# Sheet_1.net
KiCad netlist of a schematic drawn in Altium Designer
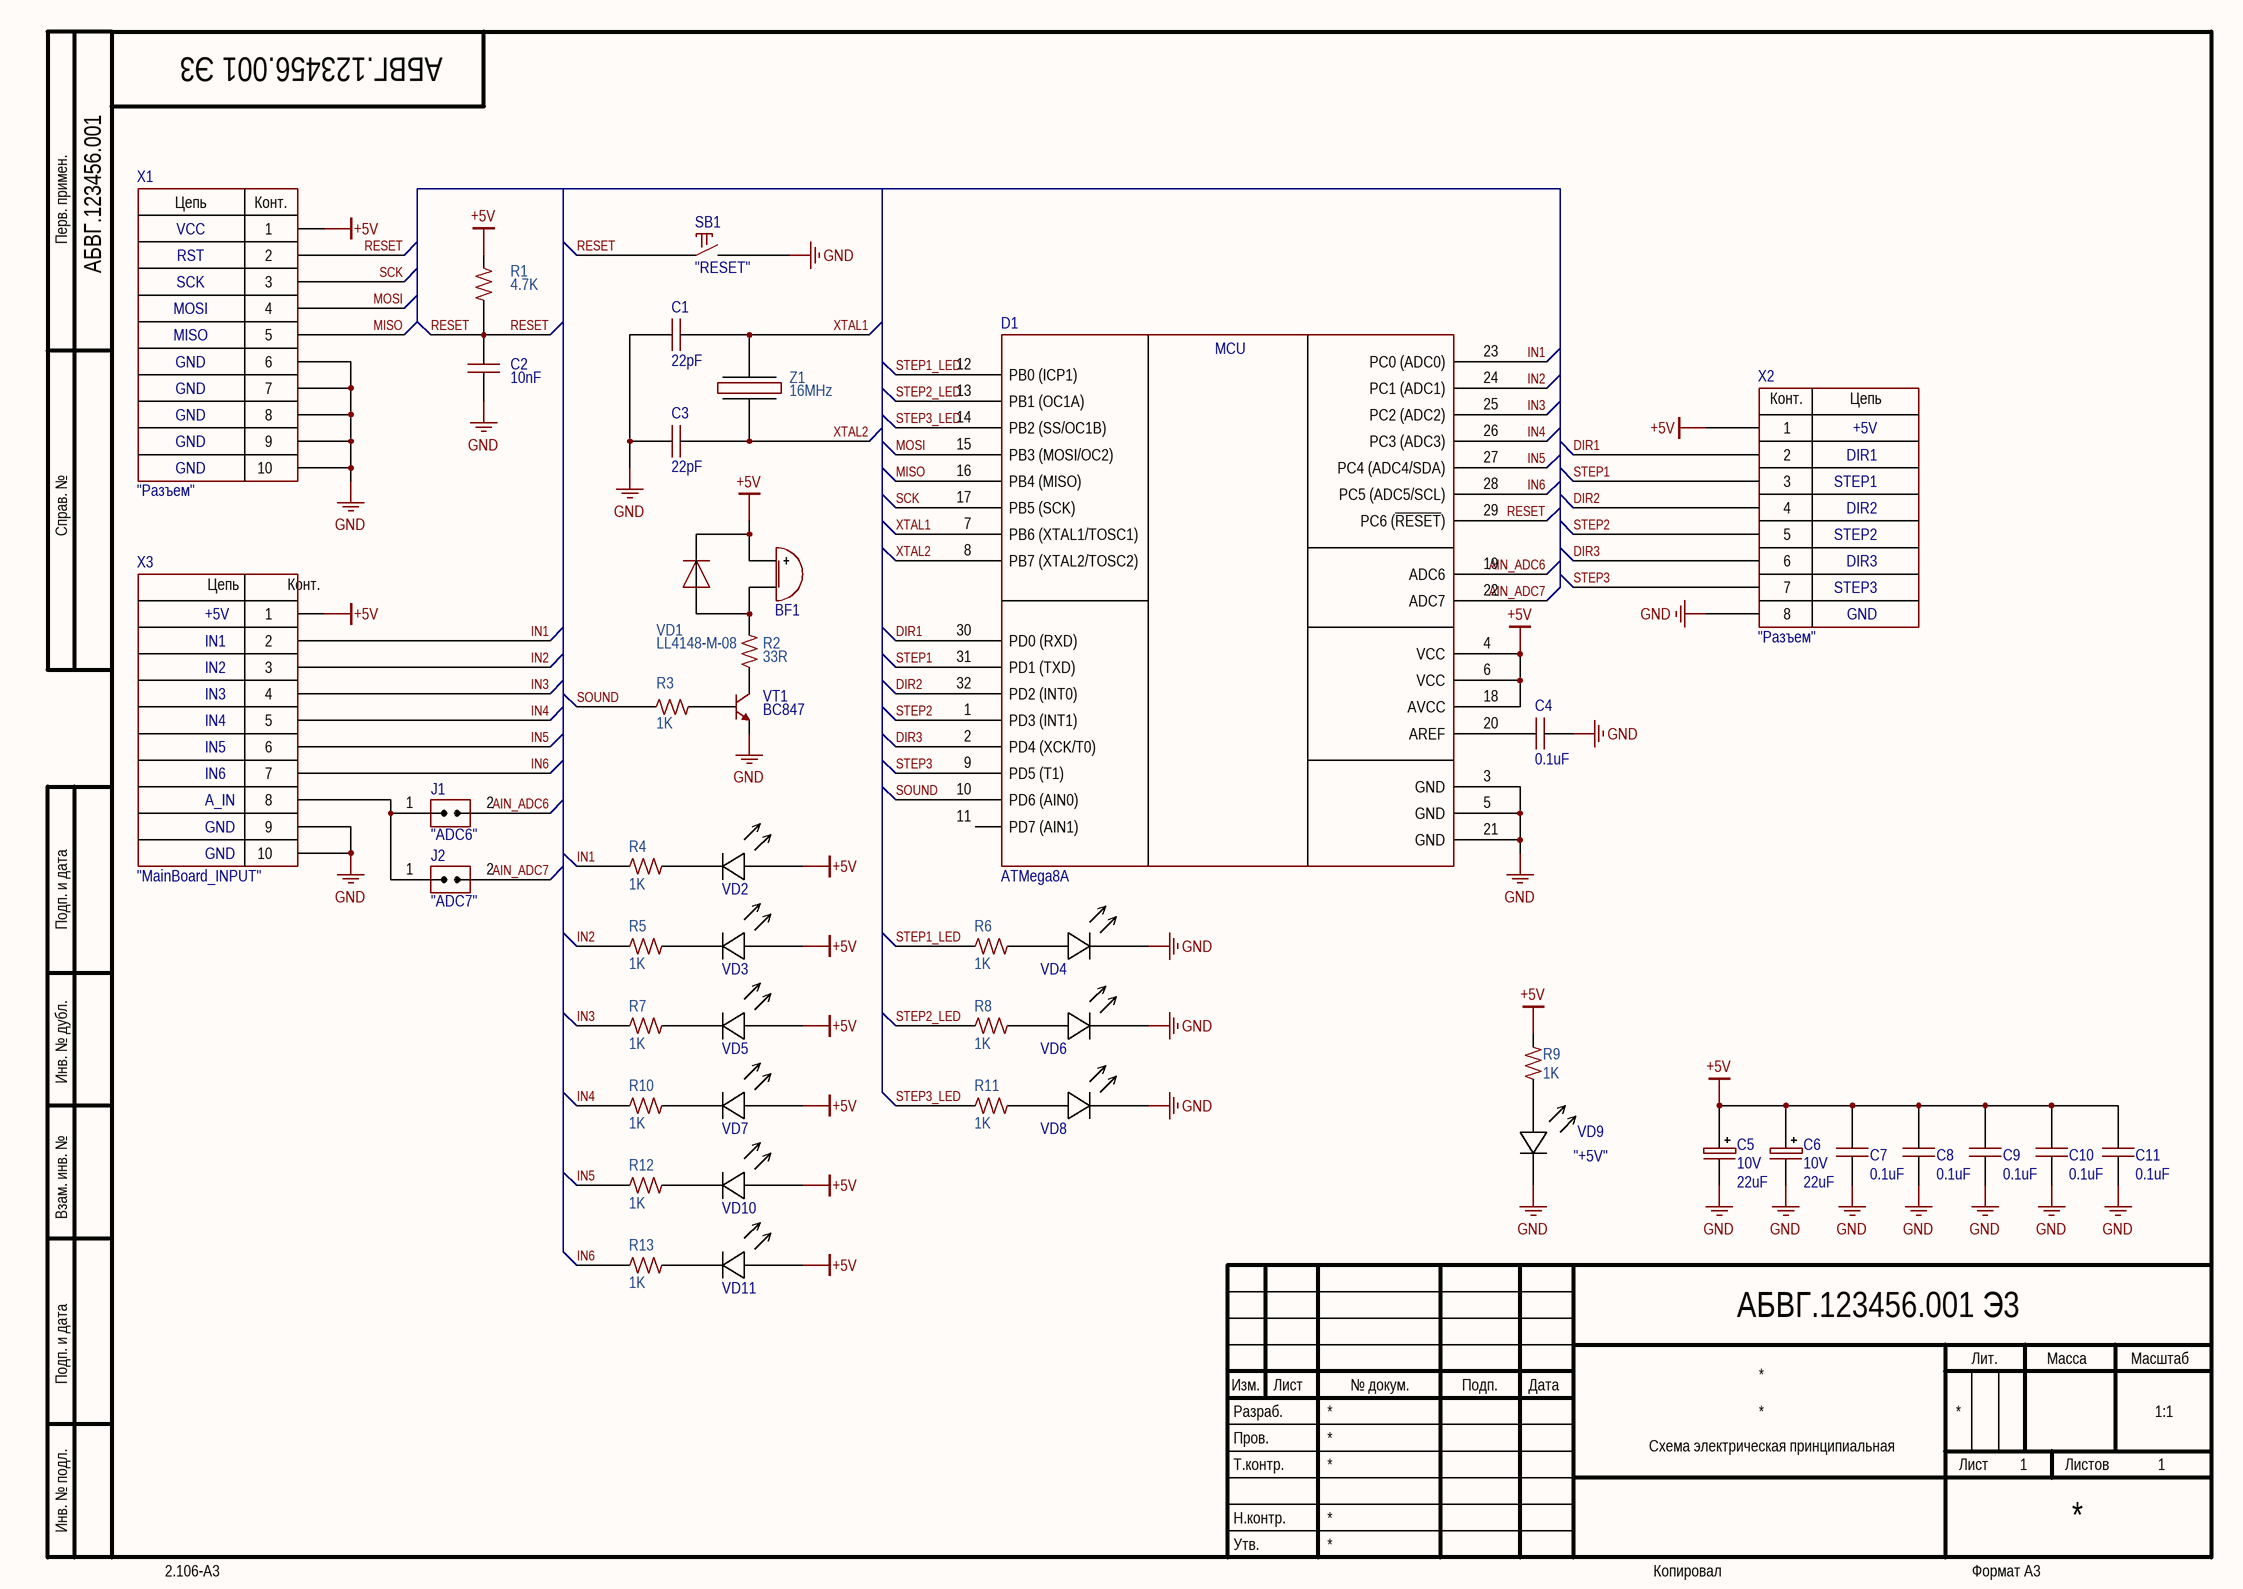
[diagram p0: Sheet_1.SchDoc]

(export (version "E")
  (design (tool "Eeschema 10.0.6"))
  (components
    (comp (ref "BF1")
      (value "~")
      (footprint "Custom_Case:BUZ: AI-1223-TWT-3V-2-R")
      (fields
        (field (name "MANUFACTURER") "PUI Audio")
        (field (name "VALUEMANUFACTURERPARTNUMBER") "DIP switch, 2.73 kHz, 3VDC, 80mA, -20...+70°C")
        (field (name "PARTNUMBER") "AT-0927-TT-6-R")
      )
      (libsource (lib "Electromechanics") (part "Buzzer"))
    )
    (comp (ref "C1")
      (value "Керамический SMD")
      (footprint "Standart_Case:CAP: 0805")
      (fields (field (name "ЗНАЧЕНИЕ") "22pF"))
      (libsource (lib "Capacitor") (part "Керамический SMD"))
    )
    (comp (ref "C2")
      (value "Керамический SMD")
      (footprint "Standart_Case:CAP: 0805")
      (fields (field (name "ЗНАЧЕНИЕ") "10nF"))
      (libsource (lib "Capacitor") (part "Керамический SMD"))
    )
    (comp (ref "C3")
      (value "Керамический SMD")
      (footprint "Standart_Case:CAP: 0805")
      (fields (field (name "ЗНАЧЕНИЕ") "22pF"))
      (libsource (lib "Capacitor") (part "Керамический SMD"))
    )
    (comp (ref "C4")
      (value "Керамический SMD")
      (footprint "Standart_Case:CAP: 0805")
      (fields (field (name "ЗНАЧЕНИЕ") "0.1uF"))
      (libsource (lib "Capacitor") (part "Керамический SMD"))
    )
    (comp (ref "C5")
      (value "~")
      (footprint "Standart_Case:CAP: TANTAL-B")
      (fields (field (name "НАПРЯЖЕНИЕ") "10V") (field (name "ЗНАЧЕНИЕ") "22uF"))
      (libsource (lib "Capacitor") (part "Танталы SMD"))
    )
    (comp (ref "C6")
      (value "~")
      (footprint "Standart_Case:CAP: TANTAL-B")
      (fields (field (name "НАПРЯЖЕНИЕ") "10V") (field (name "ЗНАЧЕНИЕ") "22uF"))
      (libsource (lib "Capacitor") (part "Танталы SMD"))
    )
    (comp (ref "C7")
      (value "Керамический SMD")
      (footprint "Standart_Case:CAP: 0805")
      (fields (field (name "ЗНАЧЕНИЕ") "0.1uF"))
      (libsource (lib "Capacitor") (part "Керамический SMD"))
    )
    (comp (ref "C8")
      (value "Керамический SMD")
      (footprint "Standart_Case:CAP: 0805")
      (fields (field (name "ЗНАЧЕНИЕ") "0.1uF"))
      (libsource (lib "Capacitor") (part "Керамический SMD"))
    )
    (comp (ref "C9")
      (value "Керамический SMD")
      (footprint "Standart_Case:CAP: 0805")
      (fields (field (name "ЗНАЧЕНИЕ") "0.1uF"))
      (libsource (lib "Capacitor") (part "Керамический SMD"))
    )
    (comp (ref "C10")
      (value "Керамический SMD")
      (footprint "Standart_Case:CAP: 0805")
      (fields (field (name "ЗНАЧЕНИЕ") "0.1uF"))
      (libsource (lib "Capacitor") (part "Керамический SMD"))
    )
    (comp (ref "C11")
      (value "Керамический SMD")
      (footprint "Standart_Case:CAP: 0805")
      (fields (field (name "ЗНАЧЕНИЕ") "0.1uF"))
      (libsource (lib "Capacitor") (part "Керамический SMD"))
    )
    (comp (ref "D1")
      (value "ATMega8A")
      (footprint "Standart_Case:32-LQFP")
      (libsource (lib "IC_MCU") (part "ATmega8"))
    )
    (comp (ref "J1")
      (value "~")
      (footprint "Custom_Case:CON: JUMPER x1")
      (fields (field (name "COMMENTTEXT") "\"ADC6\""))
      (libsource (lib "Connector") (part "Jumper_2_pin"))
    )
    (comp (ref "J2")
      (value "~")
      (footprint "Custom_Case:CON: JUMPER x1")
      (fields (field (name "COMMENTTEXT") "\"ADC7\""))
      (libsource (lib "Connector") (part "Jumper_2_pin"))
    )
    (comp (ref "R1")
      (value "4.7K")
      (footprint "Standart_Case:RES: 0805")
      (fields
        (field (name "MANUFACTURER") "Vishay Intertech")
        (field (name "PARTNUMBER") "CRCW080533R0FKEA")
        (field (name "VALUEMANUFACTURERPARTNUMBER") "Резистор SMD, 4.7K, ±1%, 0805, 0.125W, -55...+125°C")
      )
      (libsource (lib "Resistor") (part "Resistor_0805_ieee"))
    )
    (comp (ref "R2")
      (value "33R")
      (footprint "Standart_Case:RES: 0805")
      (fields
        (field (name "MANUFACTURER") "Vishay Intertech")
        (field (name "PARTNUMBER") "CRCW080533R0FKEA")
        (field (name "VALUEMANUFACTURERPARTNUMBER") "Резистор SMD, 33R, ±1%, 0805, 0.125W, -55...+125°C")
      )
      (libsource (lib "Resistor") (part "Resistor_0805_ieee"))
    )
    (comp (ref "R3")
      (value "1K")
      (footprint "Standart_Case:RES: 0805")
      (fields
        (field (name "MANUFACTURER") "Vishay Intertech")
        (field (name "PARTNUMBER") "CRCW08051K00JNEA")
        (field (name "VALUEMANUFACTURERPARTNUMBER") "Резистор SMD, 1K, ±1%, 0805, 0.125W, -55...+125°C")
      )
      (libsource (lib "Resistor") (part "Resistor_0805_ieee"))
    )
    (comp (ref "R4")
      (value "1K")
      (footprint "Standart_Case:RES: 0805")
      (fields
        (field (name "MANUFACTURER") "Vishay Intertech")
        (field (name "PARTNUMBER") "CRCW080533R0FKEA")
        (field (name "VALUEMANUFACTURERPARTNUMBER") "Резистор SMD, 1K, ±1%, 0805, 0.125W, -55...+125°C")
      )
      (libsource (lib "Resistor") (part "Resistor_0805_ieee"))
    )
    (comp (ref "R5")
      (value "1K")
      (footprint "Standart_Case:RES: 0805")
      (fields
        (field (name "MANUFACTURER") "Vishay Intertech")
        (field (name "PARTNUMBER") "CRCW080533R0FKEA")
        (field (name "VALUEMANUFACTURERPARTNUMBER") "Резистор SMD, 1K, ±1%, 0805, 0.125W, -55...+125°C")
      )
      (libsource (lib "Resistor") (part "Resistor_0805_ieee"))
    )
    (comp (ref "R6")
      (value "1K")
      (footprint "Standart_Case:RES: 0805")
      (fields
        (field (name "MANUFACTURER") "Vishay Intertech")
        (field (name "PARTNUMBER") "CRCW080533R0FKEA")
        (field (name "VALUEMANUFACTURERPARTNUMBER") "Резистор SMD, 1K, ±1%, 0805, 0.125W, -55...+125°C")
      )
      (libsource (lib "Resistor") (part "Resistor_0805_ieee"))
    )
    (comp (ref "R7")
      (value "1K")
      (footprint "Standart_Case:RES: 0805")
      (fields
        (field (name "MANUFACTURER") "Vishay Intertech")
        (field (name "PARTNUMBER") "CRCW080533R0FKEA")
        (field (name "VALUEMANUFACTURERPARTNUMBER") "Резистор SMD, 1K, ±1%, 0805, 0.125W, -55...+125°C")
      )
      (libsource (lib "Resistor") (part "Resistor_0805_ieee"))
    )
    (comp (ref "R8")
      (value "1K")
      (footprint "Standart_Case:RES: 0805")
      (fields
        (field (name "MANUFACTURER") "Vishay Intertech")
        (field (name "PARTNUMBER") "CRCW080533R0FKEA")
        (field (name "VALUEMANUFACTURERPARTNUMBER") "Резистор SMD, 1K, ±1%, 0805, 0.125W, -55...+125°C")
      )
      (libsource (lib "Resistor") (part "Resistor_0805_ieee"))
    )
    (comp (ref "R9")
      (value "1K")
      (footprint "Standart_Case:RES: 0805")
      (fields
        (field (name "MANUFACTURER") "Vishay Intertech")
        (field (name "PARTNUMBER") "CRCW080533R0FKEA")
        (field (name "VALUEMANUFACTURERPARTNUMBER") "Резистор SMD, 1K, ±1%, 0805, 0.125W, -55...+125°C")
      )
      (libsource (lib "Resistor") (part "Resistor_0805_ieee"))
    )
    (comp (ref "R10")
      (value "1K")
      (footprint "Standart_Case:RES: 0805")
      (fields
        (field (name "MANUFACTURER") "Vishay Intertech")
        (field (name "PARTNUMBER") "CRCW080533R0FKEA")
        (field (name "VALUEMANUFACTURERPARTNUMBER") "Резистор SMD, 1K, ±1%, 0805, 0.125W, -55...+125°C")
      )
      (libsource (lib "Resistor") (part "Resistor_0805_ieee"))
    )
    (comp (ref "R11")
      (value "1K")
      (footprint "Standart_Case:RES: 0805")
      (fields
        (field (name "MANUFACTURER") "Vishay Intertech")
        (field (name "PARTNUMBER") "CRCW080533R0FKEA")
        (field (name "VALUEMANUFACTURERPARTNUMBER") "Резистор SMD, 1K, ±1%, 0805, 0.125W, -55...+125°C")
      )
      (libsource (lib "Resistor") (part "Resistor_0805_ieee"))
    )
    (comp (ref "R12")
      (value "1K")
      (footprint "Standart_Case:RES: 0805")
      (fields
        (field (name "MANUFACTURER") "Vishay Intertech")
        (field (name "PARTNUMBER") "CRCW080533R0FKEA")
        (field (name "VALUEMANUFACTURERPARTNUMBER") "Резистор SMD, 1K, ±1%, 0805, 0.125W, -55...+125°C")
      )
      (libsource (lib "Resistor") (part "Resistor_0805_ieee"))
    )
    (comp (ref "R13")
      (value "1K")
      (footprint "Standart_Case:RES: 0805")
      (fields
        (field (name "MANUFACTURER") "Vishay Intertech")
        (field (name "PARTNUMBER") "CRCW080533R0FKEA")
        (field (name "VALUEMANUFACTURERPARTNUMBER") "Резистор SMD, 1K, ±1%, 0805, 0.125W, -55...+125°C")
      )
      (libsource (lib "Resistor") (part "Resistor_0805_ieee"))
    )
    (comp (ref "SB1")
      (value "~")
      (footprint "Custom_Case:BUT: 6x6 SMD")
      (fields
        (field (name "MANUFACTURER") "TE Connectivity")
        (field (name "VALUEMANUFACTURERPARTNUMBER") "Tactile button, 6x6mm")
        (field (name "PARTNUMBER") "FSM2JSMAATR")
        (field (name "COMMENTTEXT") "\"RESET\"")
      )
      (libsource (lib "Electromechanics") (part "Button_tactile"))
    )
    (comp (ref "VD1")
      (value "~")
      (footprint "Standart_Case:DIODE: SOD80")
      (fields
        (field (name "MANUFACTURER") "Vishay Intertech")
        (field (name "VALUEMANUFACTURERPARTNUMBER") "Single diode, 75V, 150mA, 1V, 4ns, SOD-80, -55...+150°C")
        (field (name "VOLTAGE") "75V")
        (field (name "PARTNUMBER") "LL4148-M-08")
      )
      (libsource (lib "Diode") (part "Diode_single"))
    )
    (comp (ref "VD2")
      (value "~")
      (footprint "Standart_Case:LED: 3mmG")
      (fields (field (name "VALUEMANUFACTURERPARTNUMBER") "LED, Green, *, *, *, -55...+150°C"))
      (libsource (lib "Diode") (part "LED_single"))
    )
    (comp (ref "VD3")
      (value "~")
      (footprint "Standart_Case:LED: 3mmG")
      (fields (field (name "VALUEMANUFACTURERPARTNUMBER") "LED, Green, *, *, *, -55...+150°C"))
      (libsource (lib "Diode") (part "LED_single"))
    )
    (comp (ref "VD4")
      (value "~")
      (footprint "Standart_Case:LED: 3mmG")
      (fields (field (name "VALUEMANUFACTURERPARTNUMBER") "LED, Green, *, *, *, -55...+150°C"))
      (libsource (lib "") (part "LED_single_1"))
    )
    (comp (ref "VD5")
      (value "~")
      (footprint "Standart_Case:LED: 3mmG")
      (fields (field (name "VALUEMANUFACTURERPARTNUMBER") "LED, Green, *, *, *, -55...+150°C"))
      (libsource (lib "Diode") (part "LED_single"))
    )
    (comp (ref "VD6")
      (value "~")
      (footprint "Standart_Case:LED: 3mmG")
      (fields (field (name "VALUEMANUFACTURERPARTNUMBER") "LED, Green, *, *, *, -55...+150°C"))
      (libsource (lib "") (part "LED_single_1"))
    )
    (comp (ref "VD7")
      (value "~")
      (footprint "Standart_Case:LED: 3mmG")
      (fields (field (name "VALUEMANUFACTURERPARTNUMBER") "LED, Green, *, *, *, -55...+150°C"))
      (libsource (lib "Diode") (part "LED_single"))
    )
    (comp (ref "VD8")
      (value "~")
      (footprint "Standart_Case:LED: 3mmG")
      (fields (field (name "VALUEMANUFACTURERPARTNUMBER") "LED, Green, *, *, *, -55...+150°C"))
      (libsource (lib "") (part "LED_single_1"))
    )
    (comp (ref "VD9")
      (value "\"+5V\"")
      (footprint "Standart_Case:LED: 3mmB")
      (fields (field (name "VALUEMANUFACTURERPARTNUMBER") "LED, Green, *, *, *, -55...+150°C"))
      (libsource (lib "Diode") (part "LED_single"))
    )
    (comp (ref "VD10")
      (value "~")
      (footprint "Standart_Case:LED: 3mmG")
      (fields (field (name "VALUEMANUFACTURERPARTNUMBER") "LED, Green, *, *, *, -55...+150°C"))
      (libsource (lib "Diode") (part "LED_single"))
    )
    (comp (ref "VD11")
      (value "~")
      (footprint "Standart_Case:LED: 3mmG")
      (fields (field (name "VALUEMANUFACTURERPARTNUMBER") "LED, Green, *, *, *, -55...+150°C"))
      (libsource (lib "Diode") (part "LED_single"))
    )
    (comp (ref "VT1")
      (value "~")
      (footprint "Standart_Case:SOT23")
      (fields
        (field (name "MANUFACTURER") "ON Semiconductor")
        (field (name "VALUEMANUFACTURERPARTNUMBER") "NPN transistor, 45V, 100mA, 100MHz, 300mW, 0.6V, 420, SOT-23, -55...+125°C")
        (field (name "PARTNUMBER") "BC847")
      )
      (libsource (lib "Transistor") (part "BJT_NPN_123"))
    )
    (comp (ref "X1")
      (value "~")
      (footprint "Custom_Case:CON: PROG(PCB) ISP")
      (fields
        (field (name "MANUFACTURER") "Connfly")
        (field (name "VALUEMANUFACTURERPARTNUMBER") "Connector, 6pin, 2.54mm, 250VAC, 3A")
        (field (name "PARTNUMBER") "IDC-6")
        (field (name "COMMENTTEXT") "\"Разъем\"")
      )
      (libsource (lib "Connector") (part "Connector_ISP_PCB"))
    )
    (comp (ref "X2")
      (value "~")
      (footprint "Custom_Case:CON: PLS-8")
      (fields
        (field (name "MANUFACTURER") "Connfly")
        (field (name "VALUEMANUFACTURERPARTNUMBER") "Connector, 8pin, 2.54mm, 500VAC, 3A")
        (field (name "PARTNUMBER") "PLS-8")
        (field (name "COMMENTTEXT") "\"Разъем\"")
      )
      (libsource (lib "Connector") (part "PLS-8"))
    )
    (comp (ref "X3")
      (value "~")
      (footprint "Custom_Case:CON: PLS-10")
      (fields
        (field (name "MANUFACTURER") "Connfly")
        (field (name "VALUEMANUFACTURERPARTNUMBER") "Connector, 10pin, 2.54mm, 500VAC, 3A")
        (field (name "PARTNUMBER") "PLS-10")
        (field (name "COMMENTTEXT") "\"MainBoard_INPUT\"")
      )
      (libsource (lib "Connector") (part "PLS-10"))
    )
    (comp (ref "Z1")
      (value "~")
      (footprint "Custom_Case:OSC: 5032_ABM3")
      (fields
        (field (name "MANUFACTURER") "ABRACON LLC")
        (field (name "PARTNUMBER") "ABM3-16.000MHZ-D2Y-T")
        (field (name "VALUEMANUFACTURERPARTNUMBER") "Crystal, 16MHz, 18pF, ±20ppm, ABM3, -40...+85°C")
        (field (name "FREQUENCY") "16MHz")
      )
      (libsource (lib "Oscilator") (part "Crystal_5032_ABM3"))
    )
  )
  (nets
    (net (code "1") (name "+5V") (class "Default")
      (node (ref "BF1") (pin "1") (pinfunction "+_1") (pintype "passive"))
      (node (ref "C10") (pin "2") (pinfunction "2_2") (pintype "passive"))
      (node (ref "C11") (pin "2") (pinfunction "2_2") (pintype "passive"))
      (node (ref "C5") (pin "1") (pinfunction "1_1") (pintype "passive"))
      (node (ref "C6") (pin "1") (pinfunction "1_1") (pintype "passive"))
      (node (ref "C7") (pin "2") (pinfunction "2_2") (pintype "passive"))
      (node (ref "C8") (pin "2") (pinfunction "2_2") (pintype "passive"))
      (node (ref "C9") (pin "2") (pinfunction "2_2") (pintype "passive"))
      (node (ref "D1") (pin "18") (pinfunction "AVCC_18") (pintype "passive"))
      (node (ref "D1") (pin "4") (pinfunction "VCC_4") (pintype "passive"))
      (node (ref "D1") (pin "6") (pinfunction "VCC_6") (pintype "passive"))
      (node (ref "R1") (pin "1") (pinfunction "1_1") (pintype "passive"))
      (node (ref "R9") (pin "2") (pinfunction "2_2") (pintype "passive"))
      (node (ref "VD1") (pin "2") (pinfunction "2_2") (pintype "passive"))
      (node (ref "VD10") (pin "1") (pinfunction "A_1") (pintype "passive"))
      (node (ref "VD11") (pin "1") (pinfunction "A_1") (pintype "passive"))
      (node (ref "VD2") (pin "1") (pinfunction "A_1") (pintype "passive"))
      (node (ref "VD3") (pin "1") (pinfunction "A_1") (pintype "passive"))
      (node (ref "VD5") (pin "1") (pinfunction "A_1") (pintype "passive"))
      (node (ref "VD7") (pin "1") (pinfunction "A_1") (pintype "passive"))
      (node (ref "X1") (pin "1") (pinfunction "1_1") (pintype "passive"))
      (node (ref "X2") (pin "1") (pinfunction "1_1") (pintype "passive"))
      (node (ref "X3") (pin "1") (pinfunction "1_1") (pintype "passive"))
    )
    (net (code "2") (name "/AIN_ADC6") (class "Default")
      (node (ref "D1") (pin "19") (pinfunction "ADC6_19") (pintype "passive"))
      (node (ref "J1") (pin "2") (pinfunction "IN_2") (pintype "passive"))
    )
    (net (code "3") (name "/AIN_ADC7") (class "Default")
      (node (ref "D1") (pin "22") (pinfunction "ADC7_22") (pintype "passive"))
      (node (ref "J2") (pin "2") (pinfunction "IN_2") (pintype "passive"))
    )
    (net (code "4") (name "/DIR1") (class "Default")
      (node (ref "D1") (pin "30") (pinfunction "PD0_(RXD)_30") (pintype "passive"))
      (node (ref "X2") (pin "2") (pinfunction "2_2") (pintype "passive"))
    )
    (net (code "5") (name "/DIR2") (class "Default")
      (node (ref "D1") (pin "32") (pinfunction "PD2_(INT0)_32") (pintype "passive"))
      (node (ref "X2") (pin "4") (pinfunction "4_4") (pintype "power_in"))
    )
    (net (code "6") (name "/DIR3") (class "Default")
      (node (ref "D1") (pin "2") (pinfunction "PD4_(XCK/T0)_2") (pintype "passive"))
      (node (ref "X2") (pin "6") (pinfunction "6_6") (pintype "power_in"))
    )
    (net (code "7") (name "/IN1") (class "Default")
      (node (ref "D1") (pin "23") (pinfunction "PC0_(ADC0)_23") (pintype "passive"))
      (node (ref "R4") (pin "1") (pinfunction "1_1") (pintype "passive"))
      (node (ref "X3") (pin "2") (pinfunction "2_2") (pintype "passive"))
    )
    (net (code "8") (name "/IN2") (class "Default")
      (node (ref "D1") (pin "24") (pinfunction "PC1_(ADC1)_24") (pintype "passive"))
      (node (ref "R5") (pin "1") (pinfunction "1_1") (pintype "passive"))
      (node (ref "X3") (pin "3") (pinfunction "3_3") (pintype "power_in"))
    )
    (net (code "9") (name "/IN3") (class "Default")
      (node (ref "D1") (pin "25") (pinfunction "PC2_(ADC2)_25") (pintype "passive"))
      (node (ref "R7") (pin "1") (pinfunction "1_1") (pintype "passive"))
      (node (ref "X3") (pin "4") (pinfunction "4_4") (pintype "power_in"))
    )
    (net (code "10") (name "/IN4") (class "Default")
      (node (ref "D1") (pin "26") (pinfunction "PC3_(ADC3)_26") (pintype "passive"))
      (node (ref "R10") (pin "1") (pinfunction "1_1") (pintype "passive"))
      (node (ref "X3") (pin "5") (pinfunction "5_5") (pintype "power_in"))
    )
    (net (code "11") (name "/IN5") (class "Default")
      (node (ref "D1") (pin "27") (pinfunction "PC4_(ADC4/SDA)_27") (pintype "passive"))
      (node (ref "R12") (pin "1") (pinfunction "1_1") (pintype "passive"))
      (node (ref "X3") (pin "6") (pinfunction "6_6") (pintype "power_in"))
    )
    (net (code "12") (name "/IN6") (class "Default")
      (node (ref "D1") (pin "28") (pinfunction "PC5_(ADC5/SCL)_28") (pintype "passive"))
      (node (ref "R13") (pin "1") (pinfunction "1_1") (pintype "passive"))
      (node (ref "X3") (pin "7") (pinfunction "7_7") (pintype "power_in"))
    )
    (net (code "13") (name "/MISO") (class "Default")
      (node (ref "D1") (pin "16") (pinfunction "PB4_(MISO)_16") (pintype "passive"))
      (node (ref "X1") (pin "5") (pinfunction "5_5") (pintype "power_in"))
    )
    (net (code "14") (name "/MOSI") (class "Default")
      (node (ref "D1") (pin "15") (pinfunction "PB3_(MOSI/OC2)_15") (pintype "passive"))
      (node (ref "X1") (pin "4") (pinfunction "4_4") (pintype "power_in"))
    )
    (net (code "15") (name "/RESET") (class "Default")
      (node (ref "C2") (pin "1") (pinfunction "1_1") (pintype "passive"))
      (node (ref "D1") (pin "29") (pinfunction "PC6_(~{RESET})_29") (pintype "passive"))
      (node (ref "R1") (pin "2") (pinfunction "2_2") (pintype "passive"))
      (node (ref "SB1") (pin "1") (pinfunction "1_1") (pintype "passive"))
      (node (ref "X1") (pin "2") (pinfunction "2_2") (pintype "passive"))
    )
    (net (code "16") (name "/SCK") (class "Default")
      (node (ref "D1") (pin "17") (pinfunction "PB5_(SCK)_17") (pintype "passive"))
      (node (ref "X1") (pin "3") (pinfunction "3_3") (pintype "power_in"))
    )
    (net (code "17") (name "/SOUND") (class "Default")
      (node (ref "D1") (pin "10") (pinfunction "PD6_(AIN0)_10") (pintype "passive"))
      (node (ref "R3") (pin "2") (pinfunction "2_2") (pintype "passive"))
    )
    (net (code "18") (name "/STEP1") (class "Default")
      (node (ref "D1") (pin "31") (pinfunction "PD1_(TXD)_31") (pintype "passive"))
      (node (ref "X2") (pin "3") (pinfunction "3_3") (pintype "power_in"))
    )
    (net (code "19") (name "/STEP1_LED") (class "Default")
      (node (ref "D1") (pin "12") (pinfunction "PB0_(ICP1)_12") (pintype "passive"))
      (node (ref "R6") (pin "1") (pinfunction "1_1") (pintype "passive"))
    )
    (net (code "20") (name "/STEP2") (class "Default")
      (node (ref "D1") (pin "1") (pinfunction "PD3_(INT1)_1") (pintype "passive"))
      (node (ref "X2") (pin "5") (pinfunction "5_5") (pintype "power_in"))
    )
    (net (code "21") (name "/STEP2_LED") (class "Default")
      (node (ref "D1") (pin "13") (pinfunction "PB1_(OC1A)_13") (pintype "passive"))
      (node (ref "R8") (pin "1") (pinfunction "1_1") (pintype "passive"))
    )
    (net (code "22") (name "/STEP3") (class "Default")
      (node (ref "D1") (pin "9") (pinfunction "PD5_(T1)_9") (pintype "passive"))
      (node (ref "X2") (pin "7") (pinfunction "7_7") (pintype "power_in"))
    )
    (net (code "23") (name "/STEP3_LED") (class "Default")
      (node (ref "D1") (pin "14") (pinfunction "PB2_(SS/OC1B)_14") (pintype "passive"))
      (node (ref "R11") (pin "1") (pinfunction "1_1") (pintype "passive"))
    )
    (net (code "24") (name "/XTAL1") (class "Default")
      (node (ref "C1") (pin "1") (pinfunction "1_1") (pintype "passive"))
      (node (ref "D1") (pin "7") (pinfunction "PB6_(XTAL1/TOSC1)_7") (pintype "passive"))
      (node (ref "Z1") (pin "2") (pinfunction "2_2") (pintype "passive"))
    )
    (net (code "25") (name "/XTAL2") (class "Default")
      (node (ref "C3") (pin "1") (pinfunction "1_1") (pintype "passive"))
      (node (ref "D1") (pin "8") (pinfunction "PB7_(XTAL2/TOSC2)_8") (pintype "passive"))
      (node (ref "Z1") (pin "1") (pinfunction "1_1") (pintype "passive"))
    )
    (net (code "26") (name "GND") (class "Default")
      (node (ref "C1") (pin "2") (pinfunction "2_2") (pintype "passive"))
      (node (ref "C10") (pin "1") (pinfunction "1_1") (pintype "passive"))
      (node (ref "C11") (pin "1") (pinfunction "1_1") (pintype "passive"))
      (node (ref "C2") (pin "2") (pinfunction "2_2") (pintype "passive"))
      (node (ref "C3") (pin "2") (pinfunction "2_2") (pintype "passive"))
      (node (ref "C4") (pin "2") (pinfunction "2_2") (pintype "passive"))
      (node (ref "C5") (pin "2") (pinfunction "2_2") (pintype "passive"))
      (node (ref "C6") (pin "2") (pinfunction "2_2") (pintype "passive"))
      (node (ref "C7") (pin "1") (pinfunction "1_1") (pintype "passive"))
      (node (ref "C8") (pin "1") (pinfunction "1_1") (pintype "passive"))
      (node (ref "C9") (pin "1") (pinfunction "1_1") (pintype "passive"))
      (node (ref "D1") (pin "21") (pinfunction "GND_21") (pintype "passive"))
      (node (ref "D1") (pin "3") (pinfunction "GND_3") (pintype "passive"))
      (node (ref "D1") (pin "5") (pinfunction "GND_5") (pintype "passive"))
      (node (ref "SB1") (pin "2") (pinfunction "2_2") (pintype "passive"))
      (node (ref "VD4") (pin "2") (pinfunction "C_2") (pintype "passive"))
      (node (ref "VD6") (pin "2") (pinfunction "C_2") (pintype "passive"))
      (node (ref "VD8") (pin "2") (pinfunction "C_2") (pintype "passive"))
      (node (ref "VD9") (pin "2") (pinfunction "C_2") (pintype "passive"))
      (node (ref "VT1") (pin "3") (pinfunction "E_3") (pintype "passive"))
      (node (ref "X1") (pin "10") (pinfunction "10_10") (pintype "power_in"))
      (node (ref "X1") (pin "6") (pinfunction "6_6") (pintype "power_in"))
      (node (ref "X1") (pin "7") (pinfunction "7_7") (pintype "power_in"))
      (node (ref "X1") (pin "8") (pinfunction "8_8") (pintype "power_in"))
      (node (ref "X1") (pin "9") (pinfunction "9_9") (pintype "power_in"))
      (node (ref "X2") (pin "8") (pinfunction "8_8") (pintype "power_in"))
      (node (ref "X3") (pin "10") (pinfunction "10_10") (pintype "power_in"))
      (node (ref "X3") (pin "9") (pinfunction "9_9") (pintype "power_in"))
    )
    (net (code "27") (name "Net-(BF1--)") (class "Default")
      (node (ref "BF1") (pin "2") (pinfunction "-_2") (pintype "passive"))
      (node (ref "R2") (pin "1") (pinfunction "1_1") (pintype "passive"))
      (node (ref "VD1") (pin "1") (pinfunction "1_1") (pintype "passive"))
    )
    (net (code "28") (name "Net-(D1-AREF)") (class "Default")
      (node (ref "C4") (pin "1") (pinfunction "1_1") (pintype "passive"))
      (node (ref "D1") (pin "20") (pinfunction "AREF_20") (pintype "passive"))
    )
    (net (code "29") (name "Net-(J1-IN-Pad1)") (class "Default")
      (node (ref "J1") (pin "1") (pinfunction "IN_1") (pintype "passive"))
      (node (ref "J2") (pin "1") (pinfunction "IN_1") (pintype "passive"))
      (node (ref "X3") (pin "8") (pinfunction "8_8") (pintype "power_in"))
    )
    (net (code "30") (name "Net-(VD2-C)") (class "Default")
      (node (ref "R4") (pin "2") (pinfunction "2_2") (pintype "passive"))
      (node (ref "VD2") (pin "2") (pinfunction "C_2") (pintype "passive"))
    )
    (net (code "31") (name "Net-(VD3-C)") (class "Default")
      (node (ref "R5") (pin "2") (pinfunction "2_2") (pintype "passive"))
      (node (ref "VD3") (pin "2") (pinfunction "C_2") (pintype "passive"))
    )
    (net (code "32") (name "Net-(VD4-A)") (class "Default")
      (node (ref "R6") (pin "2") (pinfunction "2_2") (pintype "passive"))
      (node (ref "VD4") (pin "1") (pinfunction "A_1") (pintype "passive"))
    )
    (net (code "33") (name "Net-(VD5-C)") (class "Default")
      (node (ref "R7") (pin "2") (pinfunction "2_2") (pintype "passive"))
      (node (ref "VD5") (pin "2") (pinfunction "C_2") (pintype "passive"))
    )
    (net (code "34") (name "Net-(VD6-A)") (class "Default")
      (node (ref "R8") (pin "2") (pinfunction "2_2") (pintype "passive"))
      (node (ref "VD6") (pin "1") (pinfunction "A_1") (pintype "passive"))
    )
    (net (code "35") (name "Net-(VD7-C)") (class "Default")
      (node (ref "R10") (pin "2") (pinfunction "2_2") (pintype "passive"))
      (node (ref "VD7") (pin "2") (pinfunction "C_2") (pintype "passive"))
    )
    (net (code "36") (name "Net-(VD8-A)") (class "Default")
      (node (ref "R11") (pin "2") (pinfunction "2_2") (pintype "passive"))
      (node (ref "VD8") (pin "1") (pinfunction "A_1") (pintype "passive"))
    )
    (net (code "37") (name "Net-(VD9-A)") (class "Default")
      (node (ref "R9") (pin "1") (pinfunction "1_1") (pintype "passive"))
      (node (ref "VD9") (pin "1") (pinfunction "A_1") (pintype "passive"))
    )
    (net (code "38") (name "Net-(VD10-C)") (class "Default")
      (node (ref "R12") (pin "2") (pinfunction "2_2") (pintype "passive"))
      (node (ref "VD10") (pin "2") (pinfunction "C_2") (pintype "passive"))
    )
    (net (code "39") (name "Net-(VD11-C)") (class "Default")
      (node (ref "R13") (pin "2") (pinfunction "2_2") (pintype "passive"))
      (node (ref "VD11") (pin "2") (pinfunction "C_2") (pintype "passive"))
    )
    (net (code "40") (name "Net-(VT1-B)") (class "Default")
      (node (ref "R3") (pin "1") (pinfunction "1_1") (pintype "passive"))
      (node (ref "VT1") (pin "1") (pinfunction "B_1") (pintype "passive"))
    )
    (net (code "41") (name "Net-(VT1-C)") (class "Default")
      (node (ref "R2") (pin "2") (pinfunction "2_2") (pintype "passive"))
      (node (ref "VT1") (pin "2") (pinfunction "C_2") (pintype "passive"))
    )
    (net (code "42") (name "unconnected-(D1-PD7_(AIN1)-Pad11)") (class "Default")
      (node (ref "D1") (pin "11") (pinfunction "PD7_(AIN1)_11") (pintype "passive"))
    )
  )
)
